# Communication.net
KiCad netlist of a schematic drawn in Altium Designer
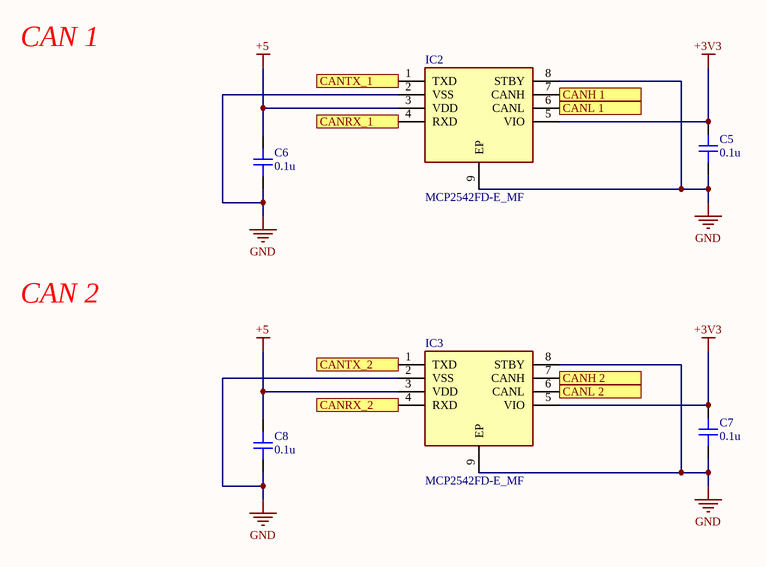
[diagram p0: Communication.SchDoc]

(export (version "E")
  (design (tool "Eeschema 10.0.6"))
  (components
    (comp (ref "C5")
      (value "0.1u")
      (footprint "CAP_0805")
      (description "Capacitor SMD 0805 10V")
      (libsource (lib "Schematic-Lib-PhilsLab") (part "CAP_0805_10V"))
    )
    (comp (ref "C6")
      (value "0.1u")
      (footprint "CAP_0805")
      (description "Capacitor SMD 0805 10V")
      (libsource (lib "Schematic-Lib-PhilsLab") (part "CAP_0805_10V"))
    )
    (comp (ref "C7")
      (value "0.1u")
      (footprint "CAP_0805")
      (description "Capacitor SMD 0805 10V")
      (libsource (lib "Schematic-Lib-PhilsLab") (part "CAP_0805_10V"))
    )
    (comp (ref "C8")
      (value "0.1u")
      (footprint "CAP_0805")
      (description "Capacitor SMD 0805 10V")
      (libsource (lib "Schematic-Lib-PhilsLab") (part "CAP_0805_10V"))
    )
    (comp (ref "IC2")
      (value "MCP2542FD-E_MF")
      (footprint "SON65P300X300X100-9N-D")
      (description "Integrated Circuit")
      (fields
        (field (name "MANUFACTURER_PART_NUMBER") "MCP2542FD-E/MF")
        (field (name "MOUSER PART NUMBER") "579-MCP2542FD-E/MF")
      )
      (libsource (lib "*") (part "MCP2542FD-E_MF"))
    )
    (comp (ref "IC3")
      (value "MCP2542FD-E_MF")
      (footprint "SON65P300X300X100-9N-D")
      (description "Integrated Circuit")
      (fields
        (field (name "MANUFACTURER_PART_NUMBER") "MCP2542FD-E/MF")
        (field (name "MOUSER PART NUMBER") "579-MCP2542FD-E/MF")
      )
      (libsource (lib "*") (part "MCP2542FD-E_MF"))
    )
  )
  (nets
    (net (code "1") (name "+3V3") (class "Default")
      (node (ref "C5") (pin "2") (pinfunction "2_2") (pintype "passive"))
      (node (ref "C7") (pin "2") (pinfunction "2_2") (pintype "passive"))
      (node (ref "IC2") (pin "5") (pinfunction "VIO_5") (pintype "passive"))
      (node (ref "IC3") (pin "5") (pinfunction "VIO_5") (pintype "passive"))
    )
    (net (code "2") (name "+5") (class "Default")
      (node (ref "C6") (pin "2") (pinfunction "2_2") (pintype "passive"))
      (node (ref "C8") (pin "2") (pinfunction "2_2") (pintype "passive"))
      (node (ref "IC2") (pin "3") (pinfunction "VDD_3") (pintype "passive"))
      (node (ref "IC3") (pin "3") (pinfunction "VDD_3") (pintype "passive"))
    )
    (net (code "3") (name "/CANH 1") (class "Default")
      (node (ref "IC2") (pin "7") (pinfunction "CANH_7") (pintype "passive"))
    )
    (net (code "4") (name "/CANH 2") (class "Default")
      (node (ref "IC3") (pin "7") (pinfunction "CANH_7") (pintype "passive"))
    )
    (net (code "5") (name "/CANL 1") (class "Default")
      (node (ref "IC2") (pin "6") (pinfunction "CANL_6") (pintype "passive"))
    )
    (net (code "6") (name "/CANL 2") (class "Default")
      (node (ref "IC3") (pin "6") (pinfunction "CANL_6") (pintype "passive"))
    )
    (net (code "7") (name "/CANRX_1") (class "Default")
      (node (ref "IC2") (pin "4") (pinfunction "RXD_4") (pintype "passive"))
    )
    (net (code "8") (name "/CANRX_2") (class "Default")
      (node (ref "IC3") (pin "4") (pinfunction "RXD_4") (pintype "passive"))
    )
    (net (code "9") (name "/CANTX_1") (class "Default")
      (node (ref "IC2") (pin "1") (pinfunction "TXD_1") (pintype "passive"))
    )
    (net (code "10") (name "/CANTX_2") (class "Default")
      (node (ref "IC3") (pin "1") (pinfunction "TXD_1") (pintype "passive"))
    )
    (net (code "11") (name "GND") (class "Default")
      (node (ref "C5") (pin "1") (pinfunction "1_1") (pintype "passive"))
      (node (ref "C6") (pin "1") (pinfunction "1_1") (pintype "passive"))
      (node (ref "C7") (pin "1") (pinfunction "1_1") (pintype "passive"))
      (node (ref "C8") (pin "1") (pinfunction "1_1") (pintype "passive"))
      (node (ref "IC2") (pin "2") (pinfunction "VSS_2") (pintype "passive"))
      (node (ref "IC2") (pin "8") (pinfunction "STBY_8") (pintype "passive"))
      (node (ref "IC2") (pin "9") (pinfunction "EP_9") (pintype "passive"))
      (node (ref "IC3") (pin "2") (pinfunction "VSS_2") (pintype "passive"))
      (node (ref "IC3") (pin "8") (pinfunction "STBY_8") (pintype "passive"))
      (node (ref "IC3") (pin "9") (pinfunction "EP_9") (pintype "passive"))
    )
  )
)
